# UCC-.net
KiCad netlist of a schematic drawn in EasyEDA Pro
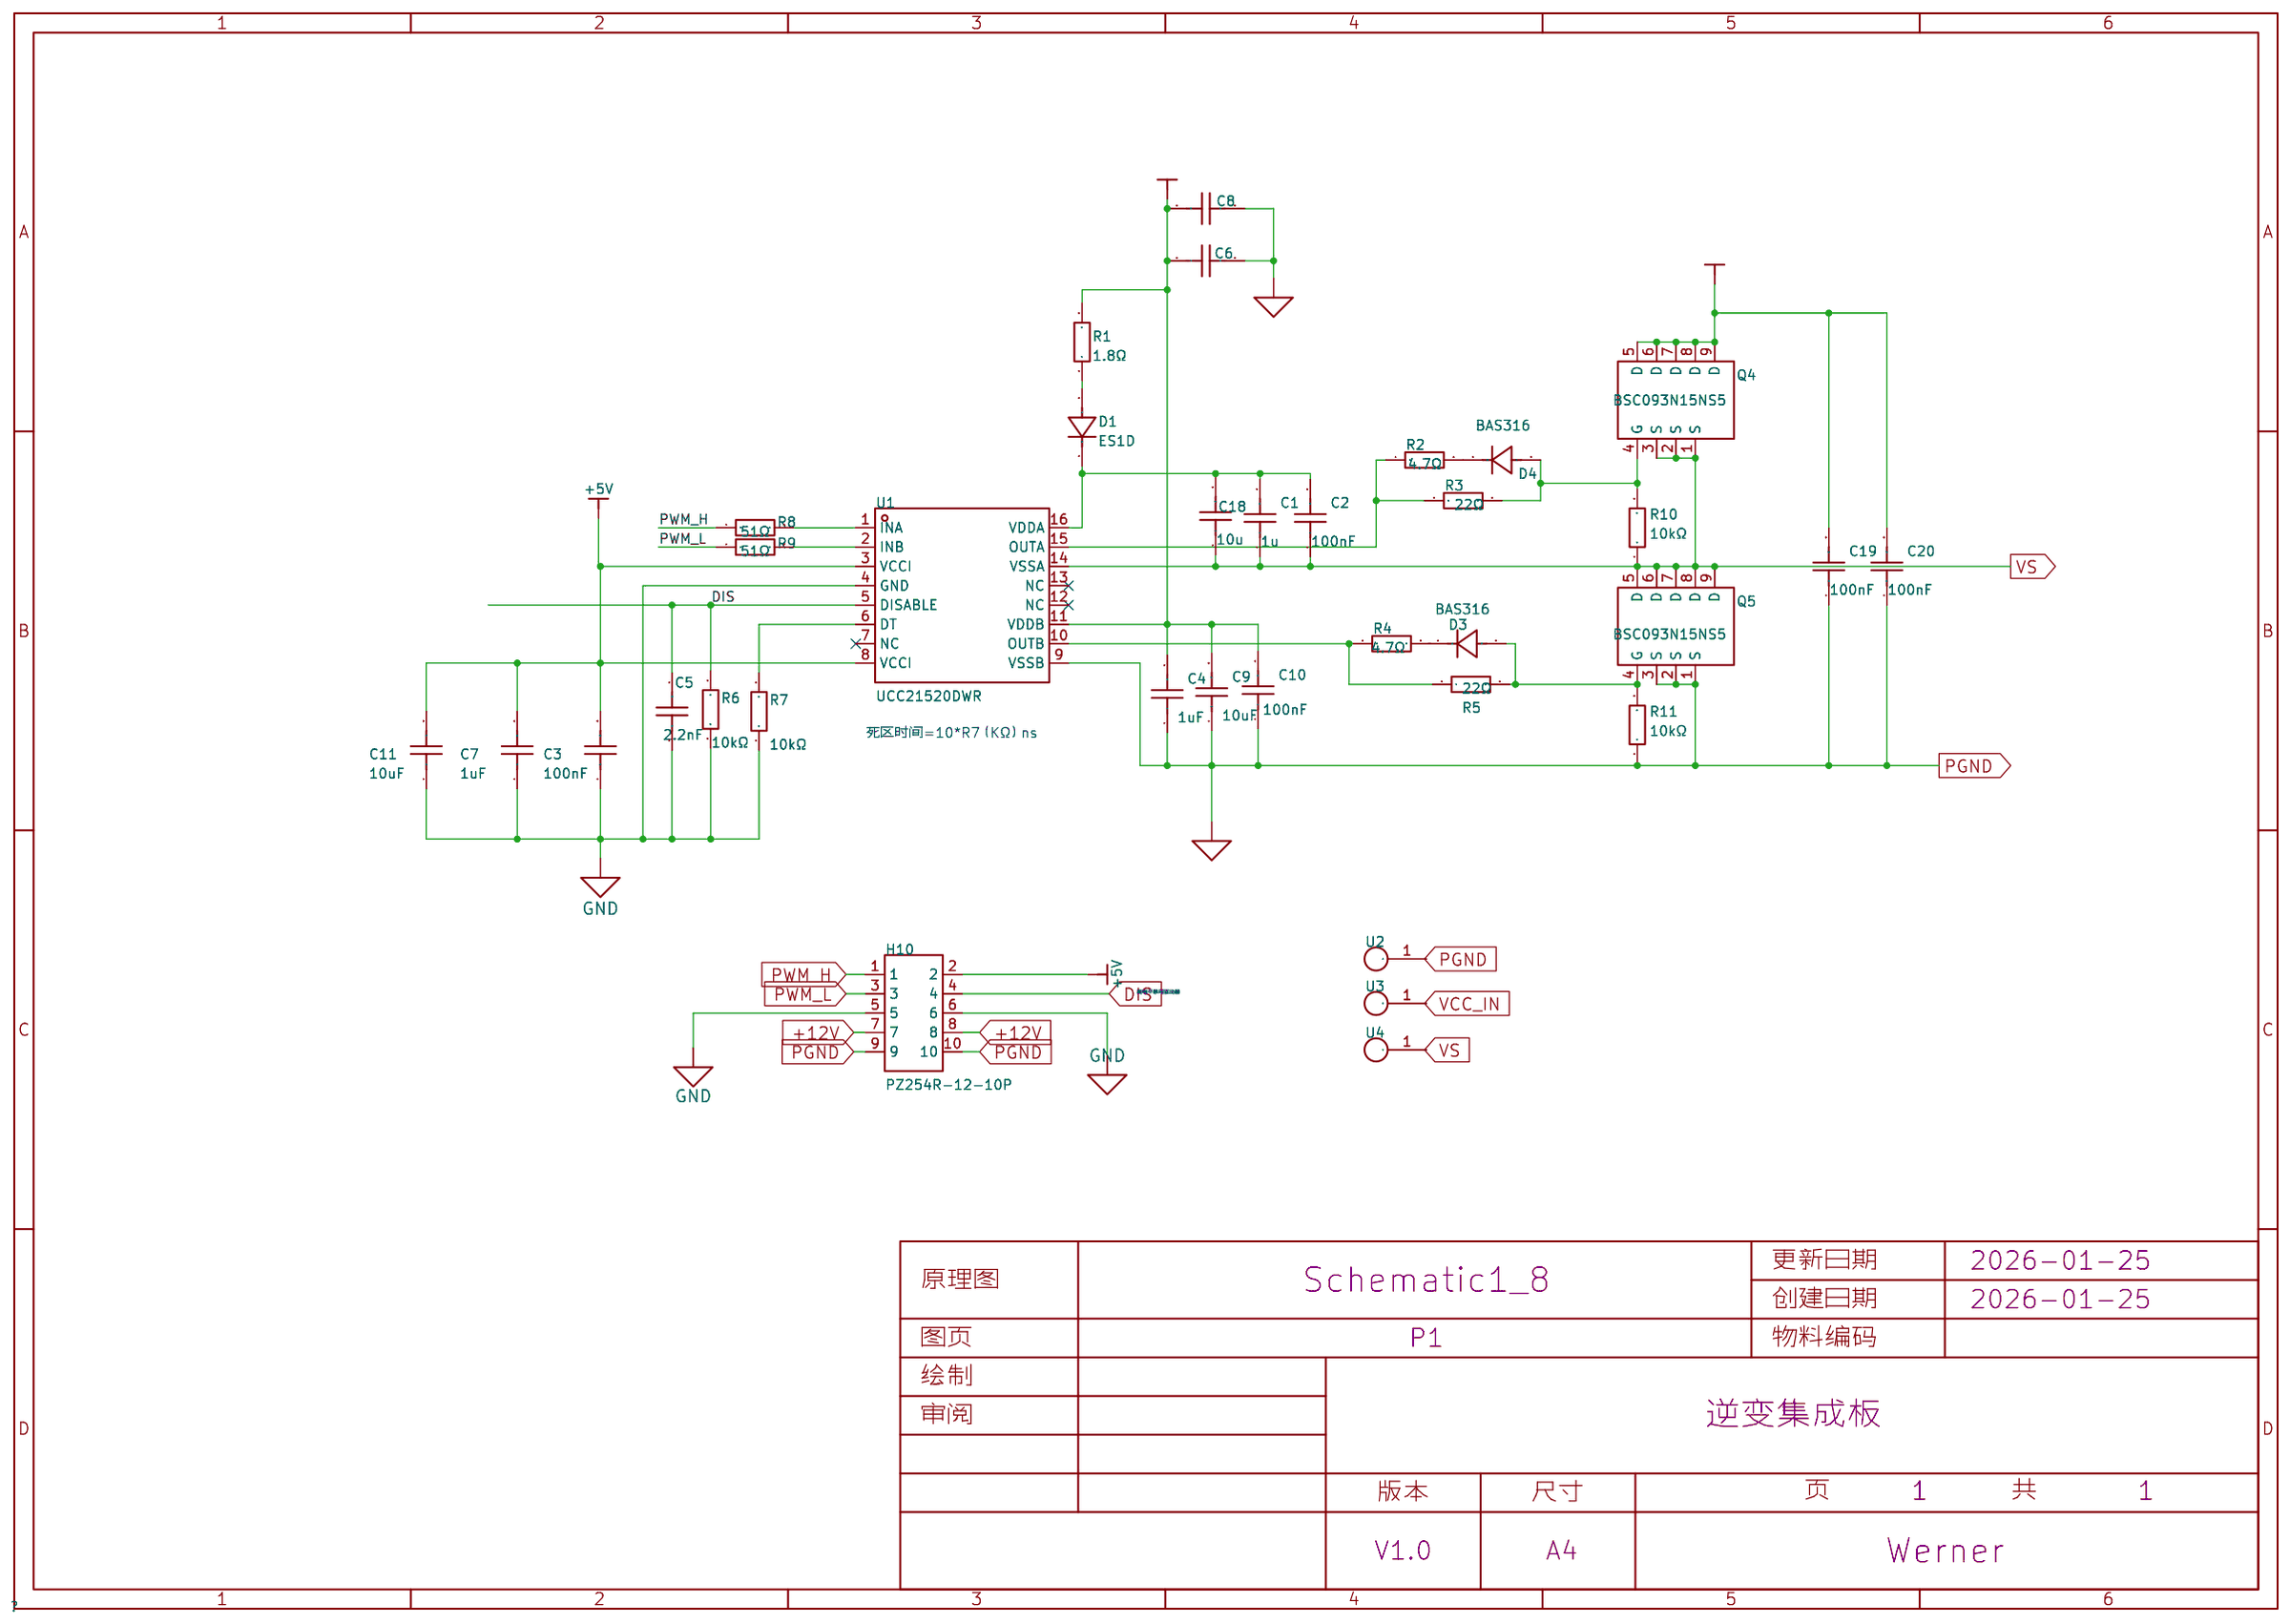
[diagram p0: schematic sheet]

(export (version "E")
  (design (tool "Eeschema 10.0.6"))
  (components
    (comp (ref "C1")
      (value "1u")
      (footprint "easyedapro:C0805")
      (libsource (lib "easyedapro") (part "Capacitance"))
    )
    (comp (ref "C2")
      (value "100nF")
      (footprint "easyedapro:C0805")
      (libsource (lib "easyedapro") (part "Capacitance"))
    )
    (comp (ref "C3")
      (value "100nF")
      (fields
        (field (name "Manufacturer Part") "CC0603KRX7R9BB104")
        (field (name "Manufacturer") "YAGEO(国巨)")
      )
      (libsource (lib "easyedapro") (part "CapAcitance"))
    )
    (comp (ref "C4")
      (value "1uF")
      (fields
        (field (name "Manufacturer Part") "CL10A105KB8NNNC")
        (field (name "Manufacturer") "SAMSUNG(三星)")
      )
      (libsource (lib "easyedapro") (part "CapAcitance"))
    )
    (comp (ref "C5")
      (value "2.2nF")
      (fields
        (field (name "Manufacturer Part") "CL10B102KB8NNNC")
        (field (name "Manufacturer") "SAMSUNG(三星)")
      )
      (libsource (lib "easyedapro") (part "CapAcitance"))
    )
    (comp (ref "C6")
      (value "1uF")
      (description "容值:1uF;精度:±10%;额定电压:50V;温度系数:X5R;")
      (libsource (lib "easyedapro") (part "CapAcitance"))
    )
    (comp (ref "C7")
      (value "1uF")
      (fields
        (field (name "Manufacturer Part") "CL10A105KB8NNNC")
        (field (name "Manufacturer") "SAMSUNG(三星)")
      )
      (libsource (lib "easyedapro") (part "CapAcitance"))
    )
    (comp (ref "C8")
      (value "10uF")
      (description "容值:10uF;精度:±10%;额定电压:10V;温度系数:X5R;")
      (libsource (lib "easyedapro") (part "CapAcitance"))
    )
    (comp (ref "C9")
      (value "10uF")
      (fields
        (field (name "Manufacturer Part") "CL10A106KP8NNNC")
        (field (name "Manufacturer") "SAMSUNG(三星)")
      )
      (libsource (lib "easyedapro") (part "CapAcitance"))
    )
    (comp (ref "C10")
      (value "100nF")
      (fields
        (field (name "Manufacturer Part") "CC0603KRX7R9BB104")
        (field (name "Manufacturer") "YAGEO(国巨)")
      )
      (libsource (lib "easyedapro") (part "CapAcitance"))
    )
    (comp (ref "C11")
      (value "10uF")
      (fields
        (field (name "Manufacturer Part") "CL10A106KP8NNNC")
        (field (name "Manufacturer") "SAMSUNG(三星)")
      )
      (libsource (lib "easyedapro") (part "CapAcitance"))
    )
    (comp (ref "C18")
      (value "10u")
      (footprint "easyedapro:C0805")
      (libsource (lib "easyedapro") (part "Capacitance"))
    )
    (comp (ref "C19")
      (value "100nF")
      (footprint "easyedapro:C0805")
      (libsource (lib "easyedapro") (part "Capacitance"))
    )
    (comp (ref "C20")
      (value "100nF")
      (footprint "easyedapro:C0805")
      (libsource (lib "easyedapro") (part "Capacitance"))
    )
    (comp (ref "D1")
      (value "ES1D")
      (footprint "easyedapro:SMA_L4.3-W2.6-LS5.0-RD")
      (fields (field (name "Manufacturer") "宏嘉诚"))
      (libsource (lib "easyedapro") (part "ES1D_C18199158"))
    )
    (comp (ref "D3")
      (value "BAS316")
      (footprint "easyedapro:SOD-323_L1.7-W1.3-LS2.6-RD-1")
      (fields (field (name "Manufacturer") "宏迦橙"))
      (libsource (lib "easyedapro") (part "BAS316_C7502720"))
    )
    (comp (ref "D4")
      (value "BAS316")
      (footprint "easyedapro:SOD-323_L1.7-W1.3-LS2.6-RD-1")
      (fields (field (name "Manufacturer") "宏迦橙"))
      (libsource (lib "easyedapro") (part "BAS316_C7502720"))
    )
    (comp (ref "H10")
      (value "PZ254R-12-10P")
      (footprint "easyedapro:HDR-TH_10P-P2.54-H-M-R2-C5-S2.54")
      (fields (field (name "Manufacturer") "XFCN(兴飞)"))
      (libsource (lib "easyedapro") (part "PZ254R-12-10P"))
    )
    (comp (ref "Q4")
      (value "BSC093N15NS5")
      (footprint "easyedapro:PG-TDSON-8_L5.0-W6.0-P1.27-LS6.2-BL-EP")
      (fields (field (name "Manufacturer") "Infineon(英飞凌)"))
      (libsource (lib "easyedapro") (part "BSC093N15NS5"))
    )
    (comp (ref "Q5")
      (value "BSC093N15NS5")
      (footprint "easyedapro:PG-TDSON-8_L5.0-W6.0-P1.27-LS6.2-BL-EP")
      (fields (field (name "Manufacturer") "Infineon(英飞凌)"))
      (libsource (lib "easyedapro") (part "BSC093N15NS5"))
    )
    (comp (ref "R1")
      (value "1.8Ω")
      (footprint "easyedapro:R1206")
      (fields (field (name "Manufacturer Part") "RC0805FR-072R2L") (field (name "Manufacturer") "YAGEO(国巨)"))
      (libsource (lib "easyedapro") (part "电阻_1"))
    )
    (comp (ref "R2")
      (value "4.7Ω")
      (footprint "easyedapro:R1206")
      (libsource (lib "easyedapro") (part "电阻_1"))
    )
    (comp (ref "R3")
      (value "22Ω")
      (footprint "easyedapro:R1206")
      (libsource (lib "easyedapro") (part "电阻_1"))
    )
    (comp (ref "R4")
      (value "4.7Ω")
      (footprint "easyedapro:R1206")
      (libsource (lib "easyedapro") (part "电阻_1"))
    )
    (comp (ref "R5")
      (value "22Ω")
      (footprint "easyedapro:R1206")
      (libsource (lib "easyedapro") (part "电阻_1"))
    )
    (comp (ref "R6")
      (value "10kΩ")
      (footprint "easyedapro:R1206")
      (fields (field (name "Manufacturer Part") "RC0603FR-0710KL") (field (name "Manufacturer") "YAGEO(国巨)"))
      (libsource (lib "easyedapro") (part "电阻_1"))
    )
    (comp (ref "R7")
      (value "10kΩ")
      (footprint "easyedapro:R1206")
      (fields (field (name "Manufacturer Part") "RC0603FR-0710KL") (field (name "Manufacturer") "YAGEO(国巨)"))
      (libsource (lib "easyedapro") (part "电阻_1"))
    )
    (comp (ref "R8")
      (value "51Ω")
      (footprint "easyedapro:R1206")
      (fields
        (field (name "Manufacturer Part") "0603WAF510JT5E")
        (field (name "Manufacturer") "UNI-ROYAL(厚声)")
      )
      (libsource (lib "easyedapro") (part "电阻_1"))
    )
    (comp (ref "R9")
      (value "51Ω")
      (footprint "easyedapro:R1206")
      (fields
        (field (name "Manufacturer Part") "0603WAF510JT5E")
        (field (name "Manufacturer") "UNI-ROYAL(厚声)")
      )
      (libsource (lib "easyedapro") (part "电阻_1"))
    )
    (comp (ref "R10")
      (value "10kΩ")
      (footprint "easyedapro:R1206")
      (fields
        (field (name "Manufacturer Part") "0603WAF1002T5E")
        (field (name "Manufacturer") "UNI-ROYAL(厚声)")
      )
      (libsource (lib "easyedapro") (part "电阻_1"))
    )
    (comp (ref "R11")
      (value "10kΩ")
      (footprint "easyedapro:R1206")
      (fields
        (field (name "Manufacturer Part") "0603WAF1002T5E")
        (field (name "Manufacturer") "UNI-ROYAL(厚声)")
      )
      (libsource (lib "easyedapro") (part "电阻_1"))
    )
    (comp (ref "U1")
      (value "UCC21520DWR")
      (footprint "easyedapro:SOIC-16_L10.3-W7.5-P1.27-LS10.3-BL")
      (fields (field (name "Manufacturer") "TI(德州仪器)"))
      (libsource (lib "easyedapro") (part "UCC21520DWR"))
    )
    (comp (ref "U2")
      (value "~")
      (footprint "easyedapro:3.5mm香蕉头")
      (libsource (lib "easyedapro") (part "3.5mm香蕉头"))
    )
    (comp (ref "U3")
      (value "~")
      (footprint "easyedapro:3.5mm香蕉头")
      (libsource (lib "easyedapro") (part "3.5mm香蕉头"))
    )
    (comp (ref "U4")
      (value "~")
      (footprint "easyedapro:3.5mm香蕉头")
      (libsource (lib "easyedapro") (part "3.5mm香蕉头"))
    )
  )
  (nets
    (net (code "1") (name "+5V") (class "Default")
      (node (ref "C11") (pin "2") (pinfunction "2_2") (pintype "input"))
      (node (ref "C3") (pin "2") (pinfunction "2_2") (pintype "input"))
      (node (ref "C7") (pin "2") (pinfunction "2_2") (pintype "input"))
      (node (ref "H10") (pin "2") (pinfunction "2_2") (pintype "unspecified"))
      (node (ref "U1") (pin "3") (pinfunction "VCCI_3") (pintype "input"))
      (node (ref "U1") (pin "8") (pinfunction "VCCI_8") (pintype "input"))
    )
    (net (code "2") (name "+12V") (class "Default")
      (node (ref "C10") (pin "2") (pinfunction "2_2") (pintype "input"))
      (node (ref "C4") (pin "2") (pinfunction "2_2") (pintype "input"))
      (node (ref "C6") (pin "2") (pinfunction "2_2") (pintype "input"))
      (node (ref "C8") (pin "2") (pinfunction "2_2") (pintype "input"))
      (node (ref "C9") (pin "2") (pinfunction "2_2") (pintype "input"))
      (node (ref "H10") (pin "7") (pinfunction "7_7") (pintype "unspecified"))
      (node (ref "H10") (pin "8") (pinfunction "8_8") (pintype "unspecified"))
      (node (ref "R1") (pin "2") (pinfunction "2_2") (pintype "input"))
      (node (ref "U1") (pin "11") (pinfunction "VDDB_11") (pintype "input"))
    )
    (net (code "3") (name "DIS") (class "Default")
      (node (ref "C5") (pin "2") (pinfunction "2_2") (pintype "input"))
      (node (ref "H10") (pin "4") (pinfunction "4_4") (pintype "unspecified"))
      (node (ref "R6") (pin "1") (pinfunction "1_1") (pintype "input"))
      (node (ref "U1") (pin "5") (pinfunction "DISABLE_5") (pintype "input"))
    )
    (net (code "4") (name "GND") (class "Default")
      (node (ref "C11") (pin "1") (pinfunction "1_1") (pintype "input"))
      (node (ref "C3") (pin "1") (pinfunction "1_1") (pintype "input"))
      (node (ref "C5") (pin "1") (pinfunction "1_1") (pintype "input"))
      (node (ref "C7") (pin "1") (pinfunction "1_1") (pintype "input"))
      (node (ref "H10") (pin "5") (pinfunction "5_5") (pintype "unspecified"))
      (node (ref "H10") (pin "6") (pinfunction "6_6") (pintype "unspecified"))
      (node (ref "R6") (pin "2") (pinfunction "2_2") (pintype "input"))
      (node (ref "R7") (pin "1") (pinfunction "1_1") (pintype "input"))
      (node (ref "U1") (pin "4") (pinfunction "GND_4") (pintype "input"))
    )
    (net (code "5") (name "Net-(D1-A)") (class "Default")
      (node (ref "D1") (pin "2") (pinfunction "A_2") (pintype "unspecified"))
      (node (ref "R1") (pin "1") (pinfunction "1_1") (pintype "input"))
    )
    (net (code "6") (name "Net-(D1-K)") (class "Default")
      (node (ref "C1") (pin "2") (pinfunction "2_2") (pintype "input"))
      (node (ref "C18") (pin "2") (pinfunction "2_2") (pintype "input"))
      (node (ref "C2") (pin "2") (pinfunction "2_2") (pintype "input"))
      (node (ref "D1") (pin "1") (pinfunction "K_1") (pintype "unspecified"))
      (node (ref "U1") (pin "16") (pinfunction "VDDA_16") (pintype "input"))
    )
    (net (code "7") (name "Net-(D3-A)") (class "Default")
      (node (ref "D3") (pin "2") (pinfunction "A_2") (pintype "unspecified"))
      (node (ref "Q5") (pin "4") (pinfunction "G_4") (pintype "unspecified"))
      (node (ref "R11") (pin "2") (pinfunction "2_2") (pintype "input"))
      (node (ref "R5") (pin "2") (pinfunction "2_2") (pintype "input"))
    )
    (net (code "8") (name "Net-(D3-K)") (class "Default")
      (node (ref "D3") (pin "1") (pinfunction "K_1") (pintype "unspecified"))
      (node (ref "R4") (pin "2") (pinfunction "2_2") (pintype "input"))
    )
    (net (code "9") (name "Net-(D4-A)") (class "Default")
      (node (ref "D4") (pin "2") (pinfunction "A_2") (pintype "unspecified"))
      (node (ref "Q4") (pin "4") (pinfunction "G_4") (pintype "unspecified"))
      (node (ref "R10") (pin "2") (pinfunction "2_2") (pintype "input"))
      (node (ref "R3") (pin "2") (pinfunction "2_2") (pintype "input"))
    )
    (net (code "10") (name "Net-(D4-K)") (class "Default")
      (node (ref "D4") (pin "1") (pinfunction "K_1") (pintype "unspecified"))
      (node (ref "R2") (pin "2") (pinfunction "2_2") (pintype "input"))
    )
    (net (code "11") (name "Net-(U1-DT)") (class "Default")
      (node (ref "R7") (pin "2") (pinfunction "2_2") (pintype "input"))
      (node (ref "U1") (pin "6") (pinfunction "DT_6") (pintype "input"))
    )
    (net (code "12") (name "Net-(U1-INA)") (class "Default")
      (node (ref "R8") (pin "2") (pinfunction "2_2") (pintype "input"))
      (node (ref "U1") (pin "1") (pinfunction "INA_1") (pintype "input"))
    )
    (net (code "13") (name "Net-(U1-INB)") (class "Default")
      (node (ref "R9") (pin "2") (pinfunction "2_2") (pintype "input"))
      (node (ref "U1") (pin "2") (pinfunction "INB_2") (pintype "input"))
    )
    (net (code "14") (name "Net-(U1-OUTA)") (class "Default")
      (node (ref "R2") (pin "1") (pinfunction "1_1") (pintype "input"))
      (node (ref "R3") (pin "1") (pinfunction "1_1") (pintype "input"))
      (node (ref "U1") (pin "15") (pinfunction "OUTA_15") (pintype "input"))
    )
    (net (code "15") (name "Net-(U1-OUTB)") (class "Default")
      (node (ref "R4") (pin "1") (pinfunction "1_1") (pintype "input"))
      (node (ref "R5") (pin "1") (pinfunction "1_1") (pintype "input"))
      (node (ref "U1") (pin "10") (pinfunction "OUTB_10") (pintype "input"))
    )
    (net (code "16") (name "PGND") (class "Default")
      (node (ref "C10") (pin "1") (pinfunction "1_1") (pintype "input"))
      (node (ref "C19") (pin "1") (pinfunction "1_1") (pintype "input"))
      (node (ref "C20") (pin "1") (pinfunction "1_1") (pintype "input"))
      (node (ref "C4") (pin "1") (pinfunction "1_1") (pintype "input"))
      (node (ref "C6") (pin "1") (pinfunction "1_1") (pintype "input"))
      (node (ref "C8") (pin "1") (pinfunction "1_1") (pintype "input"))
      (node (ref "C9") (pin "1") (pinfunction "1_1") (pintype "input"))
      (node (ref "H10") (pin "10") (pinfunction "10_10") (pintype "unspecified"))
      (node (ref "H10") (pin "9") (pinfunction "9_9") (pintype "unspecified"))
      (node (ref "Q5") (pin "1") (pinfunction "S_1") (pintype "unspecified"))
      (node (ref "Q5") (pin "2") (pinfunction "S_2") (pintype "unspecified"))
      (node (ref "Q5") (pin "3") (pinfunction "S_3") (pintype "unspecified"))
      (node (ref "R11") (pin "1") (pinfunction "1_1") (pintype "input"))
      (node (ref "U1") (pin "9") (pinfunction "VSSB_9") (pintype "input"))
      (node (ref "U2") (pin "1") (pinfunction "1_1") (pintype "input"))
    )
    (net (code "17") (name "PWM_H") (class "Default")
      (node (ref "H10") (pin "1") (pinfunction "1_1") (pintype "unspecified"))
      (node (ref "R8") (pin "1") (pinfunction "1_1") (pintype "input"))
    )
    (net (code "18") (name "PWM_L") (class "Default")
      (node (ref "H10") (pin "3") (pinfunction "3_3") (pintype "unspecified"))
      (node (ref "R9") (pin "1") (pinfunction "1_1") (pintype "input"))
    )
    (net (code "19") (name "VCC_IN") (class "Default")
      (node (ref "C19") (pin "2") (pinfunction "2_2") (pintype "input"))
      (node (ref "C20") (pin "2") (pinfunction "2_2") (pintype "input"))
      (node (ref "Q4") (pin "5") (pinfunction "D_5") (pintype "unspecified"))
      (node (ref "Q4") (pin "6") (pinfunction "D_6") (pintype "unspecified"))
      (node (ref "Q4") (pin "7") (pinfunction "D_7") (pintype "unspecified"))
      (node (ref "Q4") (pin "8") (pinfunction "D_8") (pintype "unspecified"))
      (node (ref "Q4") (pin "9") (pinfunction "D_9") (pintype "unspecified"))
      (node (ref "U3") (pin "1") (pinfunction "1_1") (pintype "input"))
    )
    (net (code "20") (name "VS") (class "Default")
      (node (ref "C1") (pin "1") (pinfunction "1_1") (pintype "input"))
      (node (ref "C18") (pin "1") (pinfunction "1_1") (pintype "input"))
      (node (ref "C2") (pin "1") (pinfunction "1_1") (pintype "input"))
      (node (ref "Q4") (pin "1") (pinfunction "S_1") (pintype "unspecified"))
      (node (ref "Q4") (pin "2") (pinfunction "S_2") (pintype "unspecified"))
      (node (ref "Q4") (pin "3") (pinfunction "S_3") (pintype "unspecified"))
      (node (ref "Q5") (pin "5") (pinfunction "D_5") (pintype "unspecified"))
      (node (ref "Q5") (pin "6") (pinfunction "D_6") (pintype "unspecified"))
      (node (ref "Q5") (pin "7") (pinfunction "D_7") (pintype "unspecified"))
      (node (ref "Q5") (pin "8") (pinfunction "D_8") (pintype "unspecified"))
      (node (ref "Q5") (pin "9") (pinfunction "D_9") (pintype "unspecified"))
      (node (ref "R10") (pin "1") (pinfunction "1_1") (pintype "input"))
      (node (ref "U1") (pin "14") (pinfunction "VSSA_14") (pintype "input"))
      (node (ref "U4") (pin "1") (pinfunction "1_1") (pintype "input"))
    )
    (net (code "21") (name "unconnected-(U1-NC-Pad7)") (class "Default")
      (node (ref "U1") (pin "7") (pinfunction "NC_7") (pintype "input+no_connect"))
    )
    (net (code "22") (name "unconnected-(U1-NC-Pad12)") (class "Default")
      (node (ref "U1") (pin "12") (pinfunction "NC_12") (pintype "input+no_connect"))
    )
    (net (code "23") (name "unconnected-(U1-NC-Pad13)") (class "Default")
      (node (ref "U1") (pin "13") (pinfunction "NC_13") (pintype "input+no_connect"))
    )
  )
)
